# Newtech_Music_Board.net
KiCad netlist of a schematic drawn in EAGLE
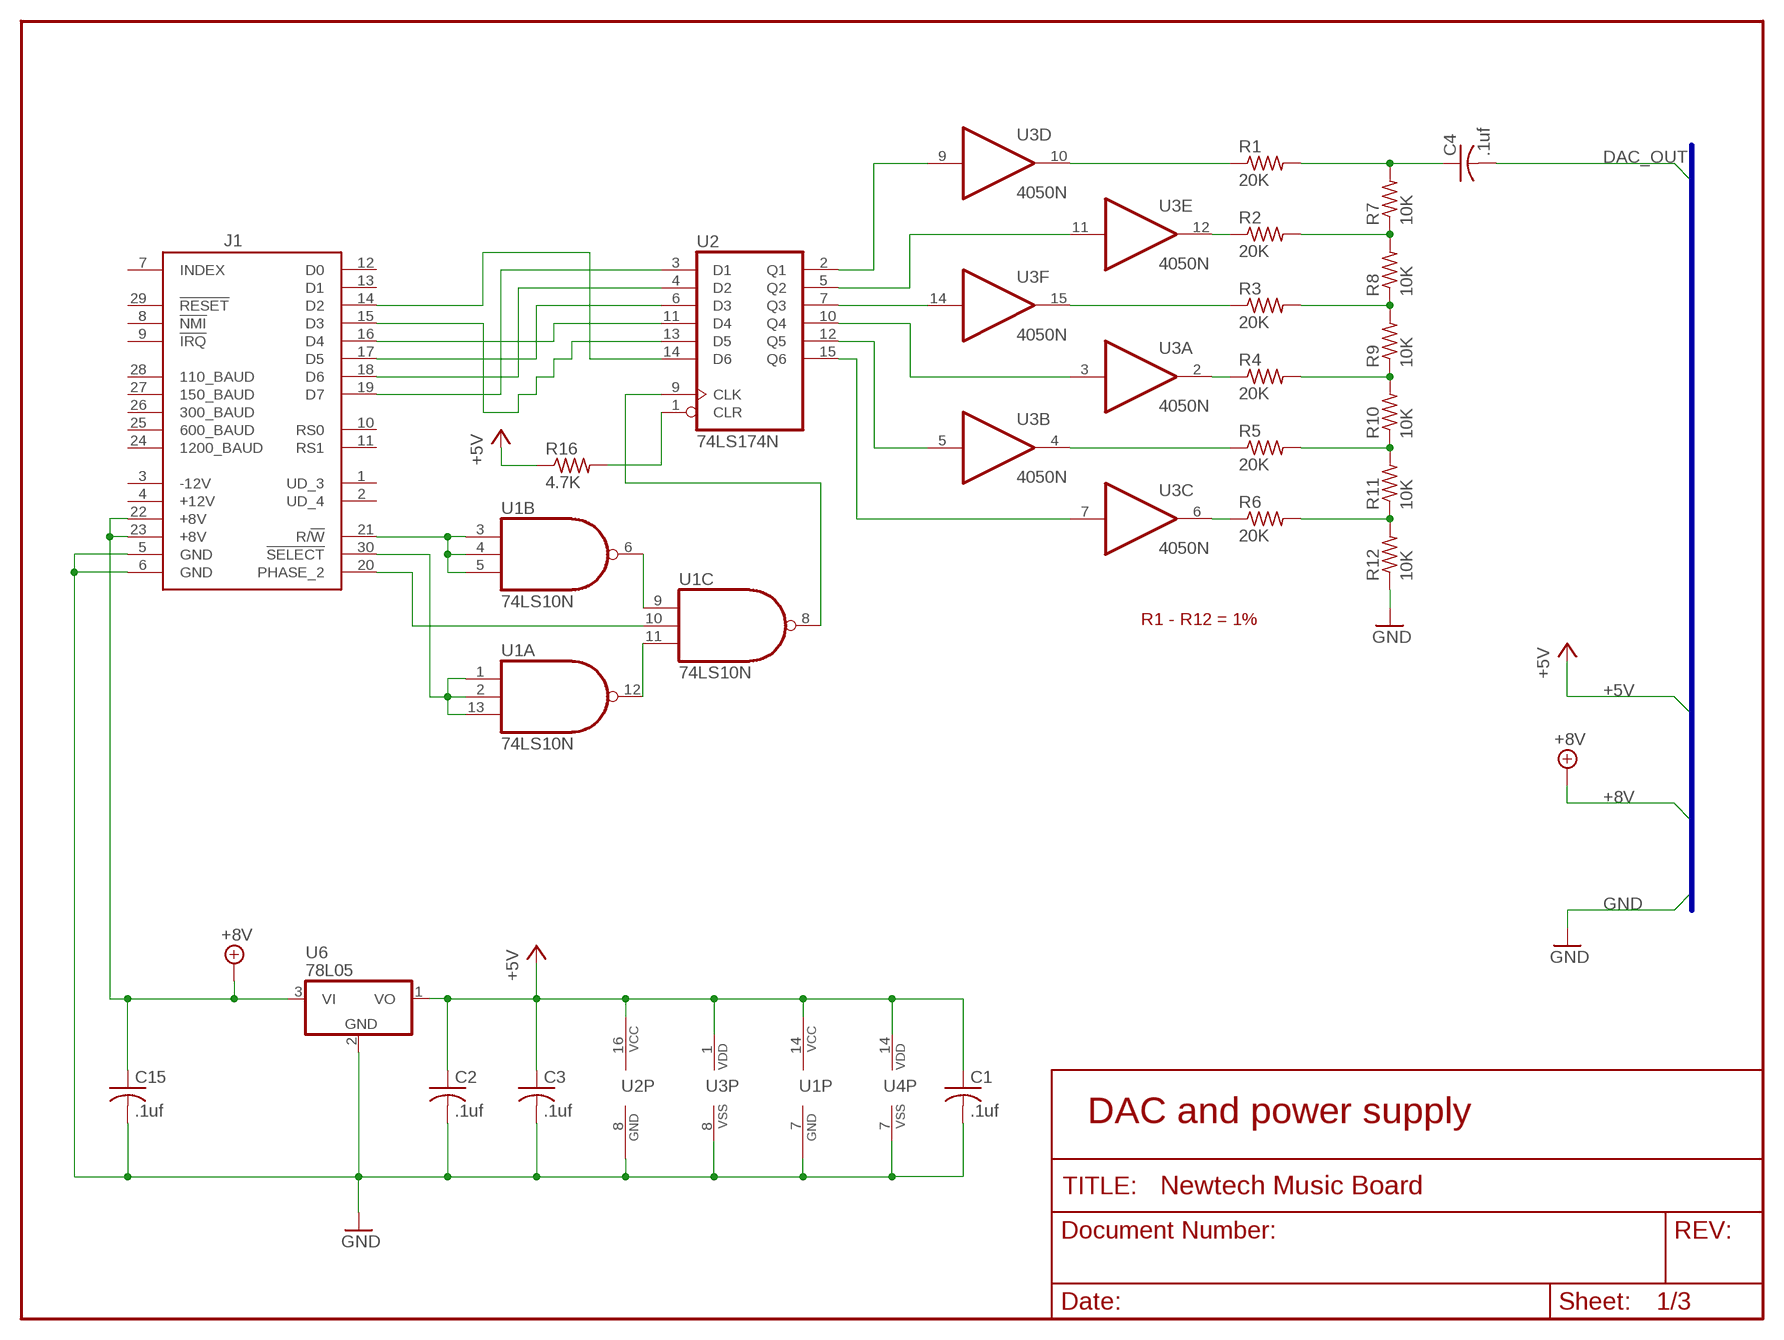
[diagram p0: schematic, sheet 1]
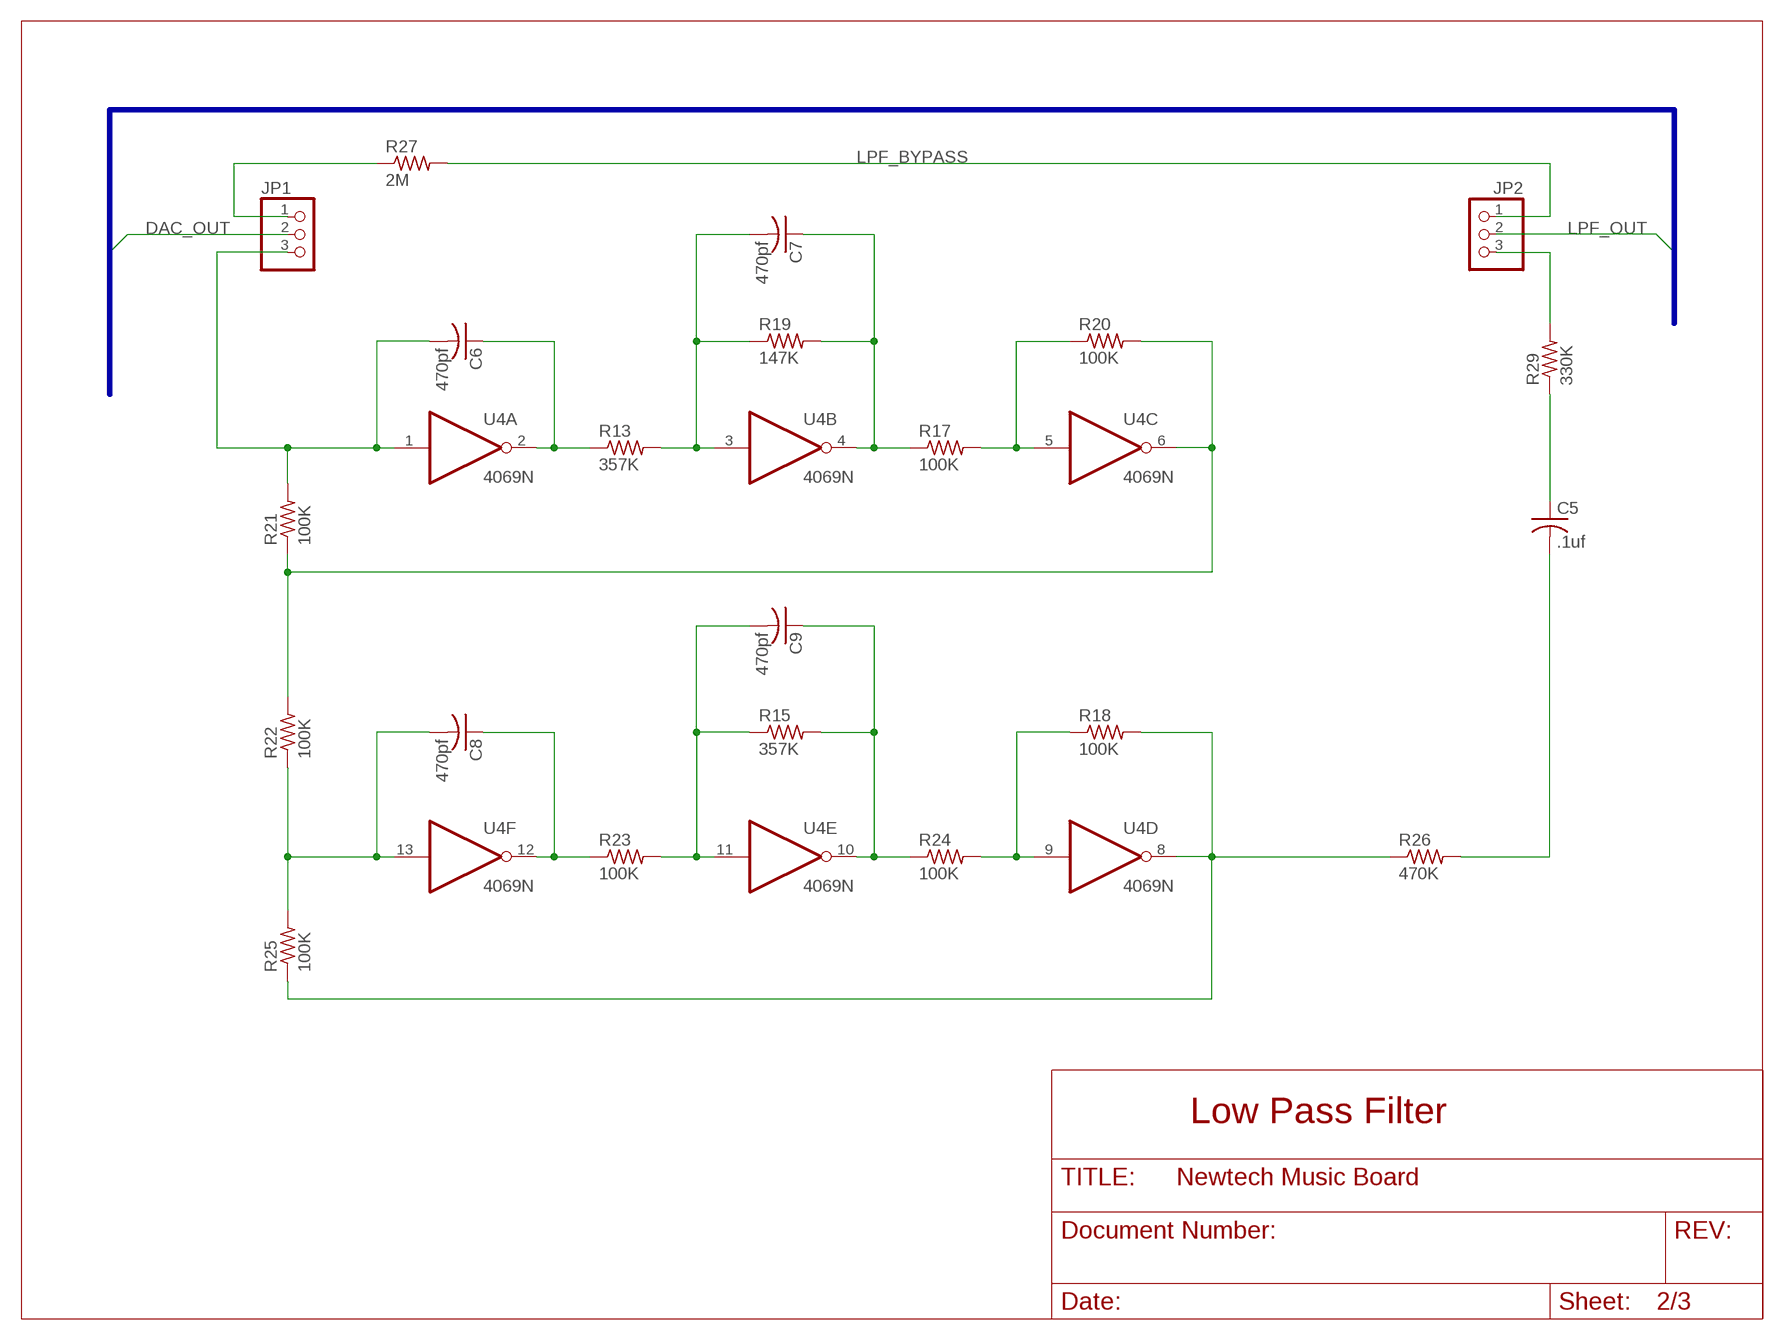
[diagram p1: schematic, sheet 2]
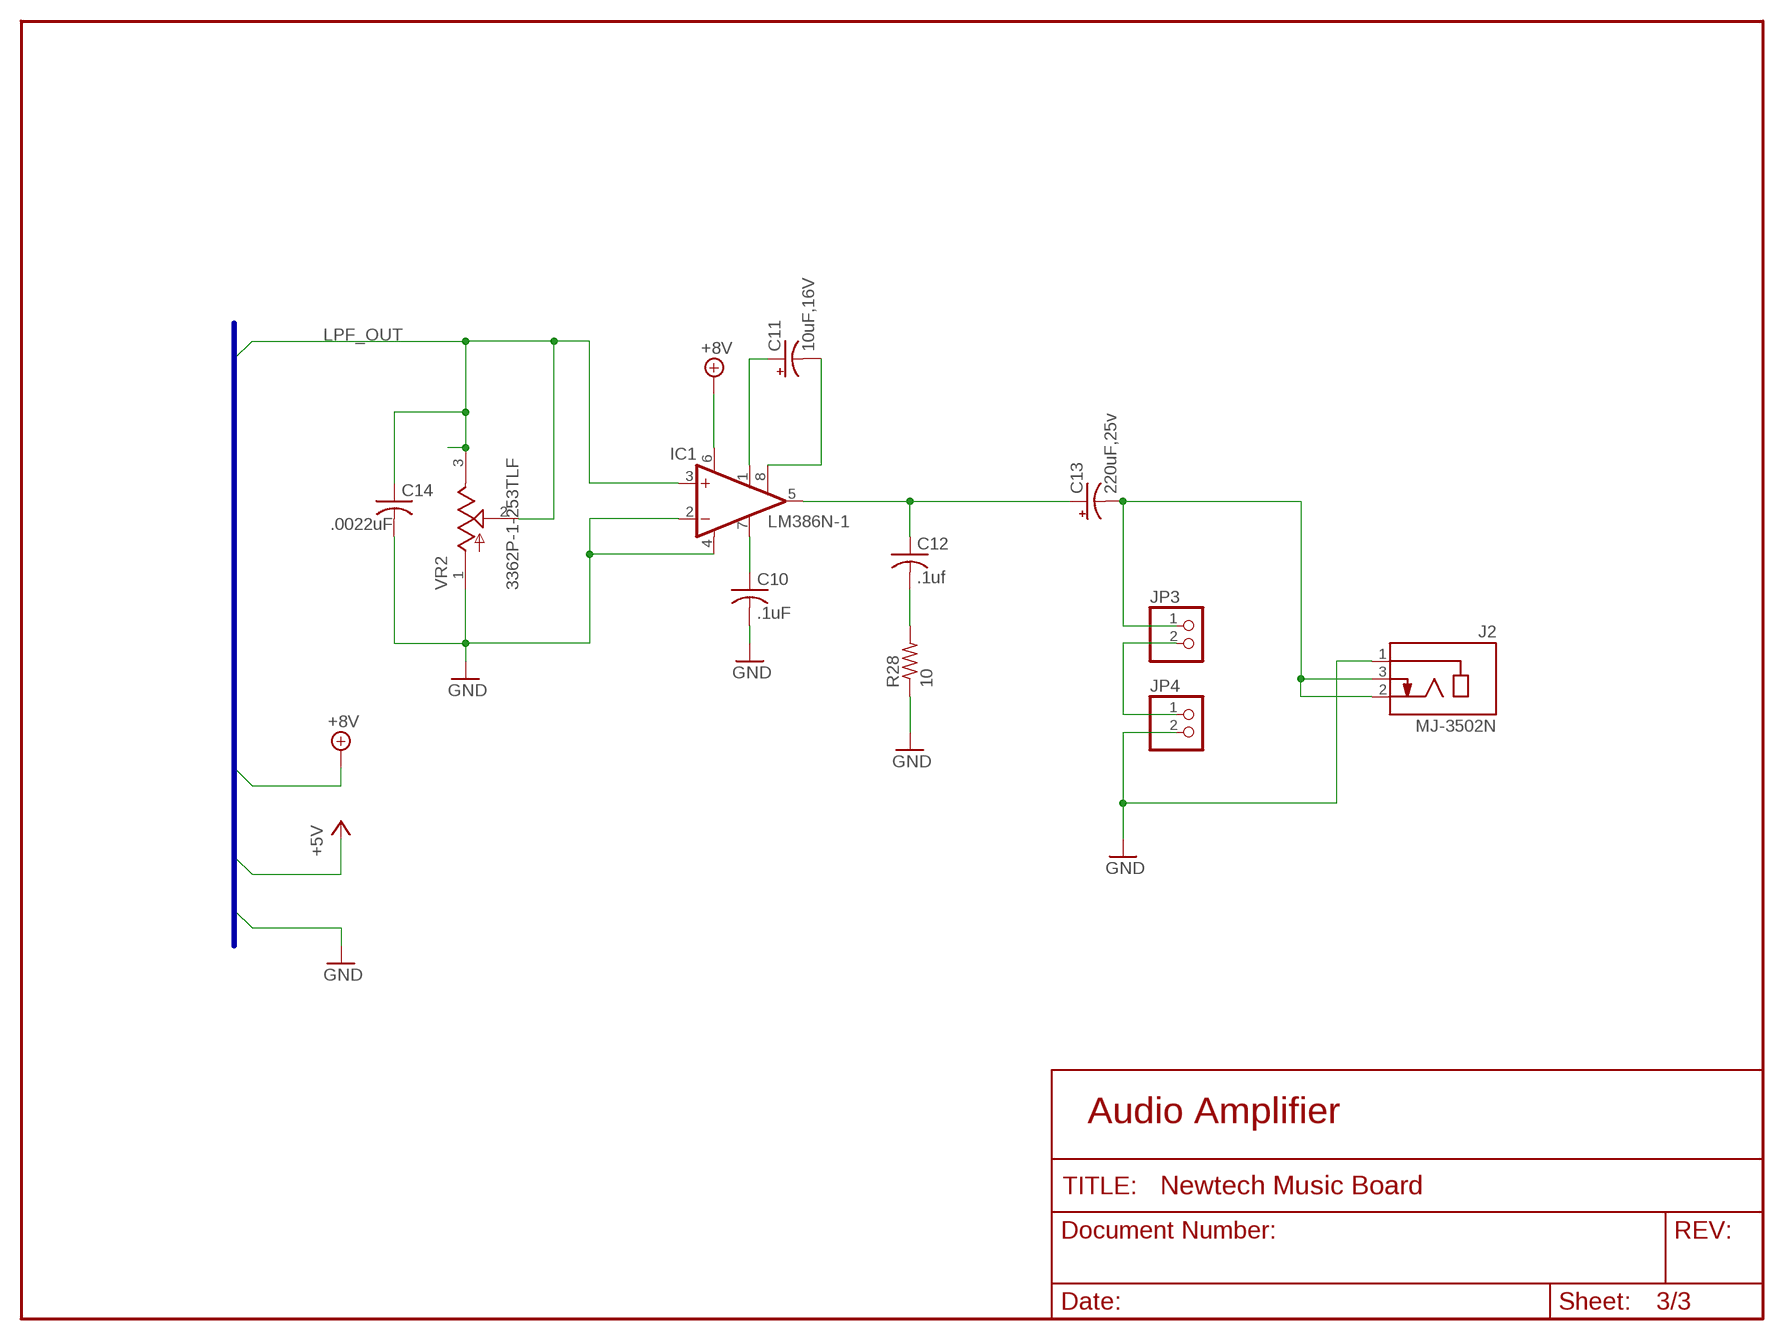
[diagram p2: schematic, sheet 3]

(export (version "E")
  (design (tool "Eeschema 10.0.6"))
  (components
    (comp (ref "C10")
      (value ".1uF")
      (footprint "eagle-import:C025-025X050")
      (libsource (lib "eagle-import") (part "rcl_334_C-US025-025X050"))
    )
    (comp (ref "C11")
      (value "10uF,16V")
      (footprint "eagle-import:E2,5-6")
      (libsource (lib "eagle-import") (part "CPOL-USE2.5-6"))
    )
    (comp (ref "C12")
      (value ".1uf")
      (footprint "eagle-import:C025-025X050")
      (libsource (lib "eagle-import") (part "C-US025-025X050"))
    )
    (comp (ref "C13")
      (value "220uF,25v")
      (footprint "eagle-import:E25-9")
      (libsource (lib "eagle-import") (part "CPOL-USE25-9AXIAL"))
    )
    (comp (ref "C14")
      (value ".0022uF")
      (footprint "eagle-import:C025-025X050")
      (libsource (lib "eagle-import") (part "C-US025-025X050"))
    )
    (comp (ref "IC1")
      (value "LM386N-1")
      (footprint "eagle-import:DIL08")
      (libsource (lib "eagle-import") (part "LM386?-N1"))
    )
    (comp (ref "J2")
      (value "MJ-3502N")
      (footprint "eagle-import:CUI_MJ-3502N")
      (fields (field (name "MF") "CUI Devices"))
      (libsource (lib "eagle-import") (part "MJ-3502N"))
    )
    (comp (ref "JP3")
      (value "PINHD-1X2")
      (footprint "eagle-import:1X02")
      (libsource (lib "eagle-import") (part "PINHD-1X2"))
    )
    (comp (ref "JP4")
      (value "PINHD-1X2")
      (footprint "eagle-import:1X02")
      (libsource (lib "eagle-import") (part "PINHD-1X2"))
    )
    (comp (ref "R28")
      (value "10")
      (footprint "eagle-import:0204_7")
      (libsource (lib "eagle-import") (part "rcl_334_R-US_0204/7"))
    )
    (comp (ref "VR2")
      (value "3362P-1-253TLF")
      (footprint "eagle-import:TRIM_3362P-1-253TLF")
      (fields (field (name "MF") "Bourns") (field (name "MP") "3362P-1-205LF"))
      (libsource (lib "eagle-import") (part "3362P-1-253TLF"))
    )
    (comp (ref "C5")
      (value ".1uf")
      (footprint "eagle-import:C025-025X050")
      (libsource (lib "eagle-import") (part "C-US025-025X050"))
    )
    (comp (ref "C6")
      (value "470pf")
      (footprint "eagle-import:C050-045X075")
      (libsource (lib "eagle-import") (part "C-US050-045X075"))
    )
    (comp (ref "C7")
      (value "470pf")
      (footprint "eagle-import:C050-045X075")
      (libsource (lib "eagle-import") (part "C-US050-045X075"))
    )
    (comp (ref "C8")
      (value "470pf")
      (footprint "eagle-import:C050-045X075")
      (libsource (lib "eagle-import") (part "C-US050-045X075"))
    )
    (comp (ref "C9")
      (value "470pf")
      (footprint "eagle-import:C050-045X075")
      (libsource (lib "eagle-import") (part "C-US050-045X075"))
    )
    (comp (ref "JP1")
      (value "PINHD-1X3")
      (footprint "eagle-import:1X03")
      (libsource (lib "eagle-import") (part "PINHD-1X3"))
    )
    (comp (ref "JP2")
      (value "PINHD-1X3")
      (footprint "eagle-import:1X03")
      (libsource (lib "eagle-import") (part "PINHD-1X3"))
    )
    (comp (ref "R13")
      (value "357K")
      (footprint "eagle-import:0204_7")
      (libsource (lib "eagle-import") (part "R-US_0204/7"))
    )
    (comp (ref "R15")
      (value "357K")
      (footprint "eagle-import:0204_7")
      (libsource (lib "eagle-import") (part "R-US_0204/7"))
    )
    (comp (ref "R17")
      (value "100K")
      (footprint "eagle-import:0204_7")
      (libsource (lib "eagle-import") (part "R-US_0204/7"))
    )
    (comp (ref "R18")
      (value "100K")
      (footprint "eagle-import:0204_7")
      (libsource (lib "eagle-import") (part "R-US_0204/7"))
    )
    (comp (ref "R19")
      (value "147K")
      (footprint "eagle-import:0204_7")
      (libsource (lib "eagle-import") (part "R-US_0204/7"))
    )
    (comp (ref "R20")
      (value "100K")
      (footprint "eagle-import:0204_7")
      (libsource (lib "eagle-import") (part "R-US_0204/7"))
    )
    (comp (ref "R21")
      (value "100K")
      (footprint "eagle-import:0204_7")
      (libsource (lib "eagle-import") (part "R-US_0204/7"))
    )
    (comp (ref "R22")
      (value "100K")
      (footprint "eagle-import:0204_7")
      (libsource (lib "eagle-import") (part "R-US_0204/7"))
    )
    (comp (ref "R23")
      (value "100K")
      (footprint "eagle-import:0204_7")
      (libsource (lib "eagle-import") (part "R-US_0204/7"))
    )
    (comp (ref "R24")
      (value "100K")
      (footprint "eagle-import:0204_7")
      (libsource (lib "eagle-import") (part "R-US_0204/7"))
    )
    (comp (ref "R25")
      (value "100K")
      (footprint "eagle-import:0204_7")
      (libsource (lib "eagle-import") (part "R-US_0204/7"))
    )
    (comp (ref "R26")
      (value "470K")
      (footprint "eagle-import:0204_7")
      (libsource (lib "eagle-import") (part "R-US_0204/7"))
    )
    (comp (ref "R27")
      (value "2M")
      (footprint "eagle-import:0204_7")
      (libsource (lib "eagle-import") (part "R-US_0204/7"))
    )
    (comp (ref "R29")
      (value "330K")
      (footprint "eagle-import:0204_7")
      (libsource (lib "eagle-import") (part "R-US_0204/7"))
    )
    (comp (ref "U4")
      (value "4069N")
      (footprint "eagle-import:DIL14")
      (libsource (lib "eagle-import") (part "4069N"))
    )
    (comp (ref "C1")
      (value ".1uf")
      (footprint "eagle-import:C025-025X050")
      (libsource (lib "eagle-import") (part "C-US025-025X050"))
    )
    (comp (ref "C2")
      (value ".1uf")
      (footprint "eagle-import:C025-025X050")
      (libsource (lib "eagle-import") (part "C-US025-025X050"))
    )
    (comp (ref "C3")
      (value ".1uf")
      (footprint "eagle-import:C025-025X050")
      (libsource (lib "eagle-import") (part "C-US025-025X050"))
    )
    (comp (ref "C4")
      (value ".1uf")
      (footprint "eagle-import:C025-024X044")
      (libsource (lib "eagle-import") (part "C-US025-024X044"))
    )
    (comp (ref "C15")
      (value ".1uf")
      (footprint "eagle-import:C025-025X050")
      (libsource (lib "eagle-import") (part "C-US025-025X050"))
    )
    (comp (ref "J1")
      (value "SS-30_BOARD_CONNECTOR")
      (footprint "eagle-import:SS-30_BOARD_CONNECTOR")
      (libsource (lib "eagle-import") (part "SS-30_BOARD_CONNECTOR"))
    )
    (comp (ref "R1")
      (value "20K")
      (footprint "eagle-import:0204_7")
      (libsource (lib "eagle-import") (part "R-US_0204/7"))
    )
    (comp (ref "R2")
      (value "20K")
      (footprint "eagle-import:0204_7")
      (libsource (lib "eagle-import") (part "R-US_0204/7"))
    )
    (comp (ref "R3")
      (value "20K")
      (footprint "eagle-import:0204_7")
      (libsource (lib "eagle-import") (part "R-US_0204/7"))
    )
    (comp (ref "R4")
      (value "20K")
      (footprint "eagle-import:0204_7")
      (libsource (lib "eagle-import") (part "R-US_0204/7"))
    )
    (comp (ref "R5")
      (value "20K")
      (footprint "eagle-import:0204_7")
      (libsource (lib "eagle-import") (part "R-US_0204/7"))
    )
    (comp (ref "R6")
      (value "20K")
      (footprint "eagle-import:0204_7")
      (libsource (lib "eagle-import") (part "R-US_0204/7"))
    )
    (comp (ref "R7")
      (value "10K")
      (footprint "eagle-import:0204_7")
      (libsource (lib "eagle-import") (part "R-US_0204/7"))
    )
    (comp (ref "R8")
      (value "10K")
      (footprint "eagle-import:0204_7")
      (libsource (lib "eagle-import") (part "R-US_0204/7"))
    )
    (comp (ref "R9")
      (value "10K")
      (footprint "eagle-import:0204_7")
      (libsource (lib "eagle-import") (part "R-US_0204/7"))
    )
    (comp (ref "R10")
      (value "10K")
      (footprint "eagle-import:0204_7")
      (libsource (lib "eagle-import") (part "R-US_0204/7"))
    )
    (comp (ref "R11")
      (value "10K")
      (footprint "eagle-import:0204_7")
      (libsource (lib "eagle-import") (part "R-US_0204/7"))
    )
    (comp (ref "R12")
      (value "10K")
      (footprint "eagle-import:0204_7")
      (libsource (lib "eagle-import") (part "R-US_0204/7"))
    )
    (comp (ref "R16")
      (value "4.7K")
      (footprint "eagle-import:0204_7")
      (libsource (lib "eagle-import") (part "R-US_0204/7"))
    )
    (comp (ref "U1")
      (value "74LS10N")
      (footprint "eagle-import:DIL14")
      (libsource (lib "eagle-import") (part "7410NLS"))
    )
    (comp (ref "U2")
      (value "74LS174N")
      (footprint "eagle-import:DIL16")
      (libsource (lib "eagle-import") (part "74174NLS"))
    )
    (comp (ref "U3")
      (value "4050N")
      (footprint "eagle-import:DIL16")
      (libsource (lib "eagle-import") (part "4050N"))
    )
    (comp (ref "U6")
      (value "78L05")
      (footprint "eagle-import:TO-92")
      (fields (field (name "MF") "STMicroelectronics") (field (name "MP") "78L05ACZ"))
      (libsource (lib "eagle-import") (part "78L05ACZ"))
    )
  )
  (nets
    (net (code "1") (name "+5V") (class "Default")
      (node (ref "C1") (pin "1") (pinfunction "1_1") (pintype "passive"))
      (node (ref "C2") (pin "1") (pinfunction "1_1") (pintype "passive"))
      (node (ref "C3") (pin "1") (pinfunction "1_1") (pintype "passive"))
      (node (ref "R16") (pin "1") (pinfunction "1_1") (pintype "passive"))
      (node (ref "U1") (pin "14") (pinfunction "VCC_14") (pintype "power_in"))
      (node (ref "U2") (pin "16") (pinfunction "VCC_16") (pintype "power_in"))
      (node (ref "U3") (pin "1") (pinfunction "VDD_1") (pintype "power_in"))
      (node (ref "U4") (pin "14") (pinfunction "VDD_14") (pintype "power_in"))
      (node (ref "U6") (pin "1") (pinfunction "VO_1") (pintype "passive"))
    )
    (net (code "2") (name "+8V") (class "Default")
      (node (ref "C15") (pin "1") (pinfunction "1_1") (pintype "passive"))
      (node (ref "IC1") (pin "6") (pinfunction "VS_6") (pintype "power_in"))
      (node (ref "J1") (pin "22") (pinfunction "+8V_22") (pintype "power_in"))
      (node (ref "J1") (pin "23") (pinfunction "+8V_23") (pintype "power_in"))
      (node (ref "U6") (pin "3") (pinfunction "VI_3") (pintype "input"))
    )
    (net (code "3") (name "+12V") (class "Default")
      (node (ref "J1") (pin "4") (pinfunction "+12V_4") (pintype "power_in"))
    )
    (net (code "4") (name "-12V") (class "Default")
      (node (ref "J1") (pin "3") (pinfunction "-12V_3") (pintype "power_in"))
    )
    (net (code "5") (name "DAC_OUT") (class "Default")
      (node (ref "C4") (pin "2") (pinfunction "2_2") (pintype "passive"))
      (node (ref "JP1") (pin "2") (pinfunction "2_2") (pintype "passive"))
    )
    (net (code "6") (name "GND") (class "Default")
      (node (ref "C1") (pin "2") (pinfunction "2_2") (pintype "passive"))
      (node (ref "C10") (pin "2") (pinfunction "2_2") (pintype "passive"))
      (node (ref "C14") (pin "2") (pinfunction "2_2") (pintype "passive"))
      (node (ref "C15") (pin "2") (pinfunction "2_2") (pintype "passive"))
      (node (ref "C2") (pin "2") (pinfunction "2_2") (pintype "passive"))
      (node (ref "C3") (pin "2") (pinfunction "2_2") (pintype "passive"))
      (node (ref "IC1") (pin "2") (pinfunction "-IN_2") (pintype "input"))
      (node (ref "IC1") (pin "4") (pinfunction "GND_4") (pintype "power_in"))
      (node (ref "J1") (pin "5") (pinfunction "GND_5") (pintype "power_in"))
      (node (ref "J1") (pin "6") (pinfunction "GND_6") (pintype "power_in"))
      (node (ref "J2") (pin "1") (pinfunction "1_1") (pintype "passive"))
      (node (ref "JP4") (pin "2") (pinfunction "2_2") (pintype "passive"))
      (node (ref "R12") (pin "1") (pinfunction "1_1") (pintype "passive"))
      (node (ref "R28") (pin "1") (pinfunction "1_1") (pintype "passive"))
      (node (ref "U1") (pin "7") (pinfunction "GND_7") (pintype "power_in"))
      (node (ref "U2") (pin "8") (pinfunction "GND_8") (pintype "power_in"))
      (node (ref "U3") (pin "8") (pinfunction "VSS_8") (pintype "power_in"))
      (node (ref "U4") (pin "7") (pinfunction "VSS_7") (pintype "power_in"))
      (node (ref "U6") (pin "2") (pinfunction "GND_2") (pintype "passive"))
      (node (ref "VR2") (pin "1") (pinfunction "CCW_1") (pintype "passive"))
    )
    (net (code "7") (name "LPF_BYPASS") (class "Default")
      (node (ref "JP2") (pin "1") (pinfunction "1_1") (pintype "passive"))
      (node (ref "R27") (pin "2") (pinfunction "2_2") (pintype "passive"))
    )
    (net (code "8") (name "LPF_OUT") (class "Default")
      (node (ref "C14") (pin "1") (pinfunction "1_1") (pintype "passive"))
      (node (ref "IC1") (pin "3") (pinfunction "+IN_3") (pintype "input"))
      (node (ref "JP2") (pin "2") (pinfunction "2_2") (pintype "passive"))
      (node (ref "VR2") (pin "2") (pinfunction "WIPER_2") (pintype "passive"))
      (node (ref "VR2") (pin "3") (pinfunction "CW_3") (pintype "passive"))
    )
    (net (code "9") (name "Net-(C4-Pad1)") (class "Default")
      (node (ref "C4") (pin "1") (pinfunction "1_1") (pintype "passive"))
      (node (ref "R1") (pin "2") (pinfunction "2_2") (pintype "passive"))
      (node (ref "R7") (pin "2") (pinfunction "2_2") (pintype "passive"))
    )
    (net (code "10") (name "Net-(C5-Pad1)") (class "Default")
      (node (ref "C5") (pin "1") (pinfunction "1_1") (pintype "passive"))
      (node (ref "R29") (pin "1") (pinfunction "1_1") (pintype "passive"))
    )
    (net (code "11") (name "Net-(C5-Pad2)") (class "Default")
      (node (ref "C5") (pin "2") (pinfunction "2_2") (pintype "passive"))
      (node (ref "R26") (pin "2") (pinfunction "2_2") (pintype "passive"))
    )
    (net (code "12") (name "Net-(C11-Pad+)") (class "Default")
      (node (ref "C11") (pin "+") (pinfunction "+_+") (pintype "passive"))
      (node (ref "IC1") (pin "1") (pinfunction "GAIN_1") (pintype "passive"))
    )
    (net (code "13") (name "Net-(C11-Pad-)") (class "Default")
      (node (ref "C11") (pin "-") (pinfunction "-_-") (pintype "passive"))
      (node (ref "IC1") (pin "8") (pinfunction "GAIN_8") (pintype "passive"))
    )
    (net (code "14") (name "Net-(C12-Pad2)") (class "Default")
      (node (ref "C12") (pin "2") (pinfunction "2_2") (pintype "passive"))
      (node (ref "R28") (pin "2") (pinfunction "2_2") (pintype "passive"))
    )
    (net (code "15") (name "Net-(C13-Pad-)") (class "Default")
      (node (ref "C13") (pin "-") (pinfunction "-_-") (pintype "passive"))
      (node (ref "J2") (pin "2") (pinfunction "2_2") (pintype "passive"))
      (node (ref "J2") (pin "3") (pinfunction "3_3") (pintype "passive"))
      (node (ref "JP3") (pin "1") (pinfunction "1_1") (pintype "passive"))
    )
    (net (code "16") (name "Net-(IC1-BYPASS)") (class "Default")
      (node (ref "C10") (pin "1") (pinfunction "1_1") (pintype "passive"))
      (node (ref "IC1") (pin "7") (pinfunction "BYPASS_7") (pintype "passive"))
    )
    (net (code "17") (name "Net-(IC1-OUT)") (class "Default")
      (node (ref "C12") (pin "1") (pinfunction "1_1") (pintype "passive"))
      (node (ref "C13") (pin "+") (pinfunction "+_+") (pintype "passive"))
      (node (ref "IC1") (pin "5") (pinfunction "OUT_5") (pintype "output"))
    )
    (net (code "18") (name "Net-(J1-D2)") (class "Default")
      (node (ref "J1") (pin "14") (pinfunction "D2_14") (pintype "bidirectional"))
      (node (ref "U2") (pin "14") (pinfunction "D6_14") (pintype "input"))
    )
    (net (code "19") (name "Net-(J1-D3)") (class "Default")
      (node (ref "J1") (pin "15") (pinfunction "D3_15") (pintype "bidirectional"))
      (node (ref "U2") (pin "13") (pinfunction "D5_13") (pintype "input"))
    )
    (net (code "20") (name "Net-(J1-D4)") (class "Default")
      (node (ref "J1") (pin "16") (pinfunction "D4_16") (pintype "bidirectional"))
      (node (ref "U2") (pin "11") (pinfunction "D4_11") (pintype "input"))
    )
    (net (code "21") (name "Net-(J1-D5)") (class "Default")
      (node (ref "J1") (pin "17") (pinfunction "D5_17") (pintype "bidirectional"))
      (node (ref "U2") (pin "6") (pinfunction "D3_6") (pintype "input"))
    )
    (net (code "22") (name "Net-(J1-D6)") (class "Default")
      (node (ref "J1") (pin "18") (pinfunction "D6_18") (pintype "bidirectional"))
      (node (ref "U2") (pin "4") (pinfunction "D2_4") (pintype "input"))
    )
    (net (code "23") (name "Net-(J1-D7)") (class "Default")
      (node (ref "J1") (pin "19") (pinfunction "D7_19") (pintype "bidirectional"))
      (node (ref "U2") (pin "3") (pinfunction "D1_3") (pintype "input"))
    )
    (net (code "24") (name "Net-(J1-PHASE_2)") (class "Default")
      (node (ref "J1") (pin "20") (pinfunction "PHASE_2_20") (pintype "bidirectional"))
      (node (ref "U1") (pin "10") (pinfunction "I1_10") (pintype "input"))
    )
    (net (code "25") (name "Net-(J1-R{slash}~{W})") (class "Default")
      (node (ref "J1") (pin "21") (pinfunction "R/~{W}_21") (pintype "bidirectional"))
      (node (ref "U1") (pin "3") (pinfunction "I0_3") (pintype "input"))
      (node (ref "U1") (pin "4") (pinfunction "I1_4") (pintype "input"))
      (node (ref "U1") (pin "5") (pinfunction "I2_5") (pintype "input"))
    )
    (net (code "26") (name "Net-(J1-~{SELECT})") (class "Default")
      (node (ref "J1") (pin "30") (pinfunction "~{SELECT}_30") (pintype "bidirectional"))
      (node (ref "U1") (pin "1") (pinfunction "I0_1") (pintype "input"))
      (node (ref "U1") (pin "13") (pinfunction "I2_13") (pintype "input"))
      (node (ref "U1") (pin "2") (pinfunction "I1_2") (pintype "input"))
    )
    (net (code "27") (name "Net-(JP1-Pad1)") (class "Default")
      (node (ref "JP1") (pin "1") (pinfunction "1_1") (pintype "passive"))
      (node (ref "R27") (pin "1") (pinfunction "1_1") (pintype "passive"))
    )
    (net (code "28") (name "Net-(JP2-Pad3)") (class "Default")
      (node (ref "JP2") (pin "3") (pinfunction "3_3") (pintype "passive"))
      (node (ref "R29") (pin "2") (pinfunction "2_2") (pintype "passive"))
    )
    (net (code "29") (name "Net-(JP3-Pad2)") (class "Default")
      (node (ref "JP3") (pin "2") (pinfunction "2_2") (pintype "passive"))
      (node (ref "JP4") (pin "1") (pinfunction "1_1") (pintype "passive"))
    )
    (net (code "30") (name "Net-(R2-Pad2)") (class "Default")
      (node (ref "R2") (pin "2") (pinfunction "2_2") (pintype "passive"))
      (node (ref "R7") (pin "1") (pinfunction "1_1") (pintype "passive"))
      (node (ref "R8") (pin "2") (pinfunction "2_2") (pintype "passive"))
    )
    (net (code "31") (name "Net-(R3-Pad2)") (class "Default")
      (node (ref "R3") (pin "2") (pinfunction "2_2") (pintype "passive"))
      (node (ref "R8") (pin "1") (pinfunction "1_1") (pintype "passive"))
      (node (ref "R9") (pin "2") (pinfunction "2_2") (pintype "passive"))
    )
    (net (code "32") (name "Net-(R10-Pad1)") (class "Default")
      (node (ref "R10") (pin "1") (pinfunction "1_1") (pintype "passive"))
      (node (ref "R11") (pin "2") (pinfunction "2_2") (pintype "passive"))
      (node (ref "R5") (pin "2") (pinfunction "2_2") (pintype "passive"))
    )
    (net (code "33") (name "Net-(R10-Pad2)") (class "Default")
      (node (ref "R10") (pin "2") (pinfunction "2_2") (pintype "passive"))
      (node (ref "R4") (pin "2") (pinfunction "2_2") (pintype "passive"))
      (node (ref "R9") (pin "1") (pinfunction "1_1") (pintype "passive"))
    )
    (net (code "34") (name "Net-(R11-Pad1)") (class "Default")
      (node (ref "R11") (pin "1") (pinfunction "1_1") (pintype "passive"))
      (node (ref "R12") (pin "2") (pinfunction "2_2") (pintype "passive"))
      (node (ref "R6") (pin "2") (pinfunction "2_2") (pintype "passive"))
    )
    (net (code "35") (name "Net-(U1A-O)") (class "Default")
      (node (ref "U1") (pin "11") (pinfunction "I2_11") (pintype "input"))
      (node (ref "U1") (pin "12") (pinfunction "O_12") (pintype "output"))
    )
    (net (code "36") (name "Net-(U1B-O)") (class "Default")
      (node (ref "U1") (pin "6") (pinfunction "O_6") (pintype "output"))
      (node (ref "U1") (pin "9") (pinfunction "I0_9") (pintype "input"))
    )
    (net (code "37") (name "Net-(U1C-O)") (class "Default")
      (node (ref "U1") (pin "8") (pinfunction "O_8") (pintype "output"))
      (node (ref "U2") (pin "9") (pinfunction "CLK_9") (pintype "input"))
    )
    (net (code "38") (name "Net-(U2A-CLR)") (class "Default")
      (node (ref "R16") (pin "2") (pinfunction "2_2") (pintype "passive"))
      (node (ref "U2") (pin "1") (pinfunction "CLR_1") (pintype "input"))
    )
    (net (code "39") (name "Net-(U2A-Q1)") (class "Default")
      (node (ref "U2") (pin "2") (pinfunction "Q1_2") (pintype "output"))
      (node (ref "U3") (pin "9") (pinfunction "I_9") (pintype "input"))
    )
    (net (code "40") (name "Net-(U2A-Q2)") (class "Default")
      (node (ref "U2") (pin "5") (pinfunction "Q2_5") (pintype "output"))
      (node (ref "U3") (pin "11") (pinfunction "I_11") (pintype "input"))
    )
    (net (code "41") (name "Net-(U2A-Q3)") (class "Default")
      (node (ref "U2") (pin "7") (pinfunction "Q3_7") (pintype "output"))
      (node (ref "U3") (pin "14") (pinfunction "I_14") (pintype "input"))
    )
    (net (code "42") (name "Net-(U2A-Q4)") (class "Default")
      (node (ref "U2") (pin "10") (pinfunction "Q4_10") (pintype "output"))
      (node (ref "U3") (pin "3") (pinfunction "I_3") (pintype "input"))
    )
    (net (code "43") (name "Net-(U2A-Q5)") (class "Default")
      (node (ref "U2") (pin "12") (pinfunction "Q5_12") (pintype "output"))
      (node (ref "U3") (pin "5") (pinfunction "I_5") (pintype "input"))
    )
    (net (code "44") (name "Net-(U2A-Q6)") (class "Default")
      (node (ref "U2") (pin "15") (pinfunction "Q6_15") (pintype "output"))
      (node (ref "U3") (pin "7") (pinfunction "I_7") (pintype "input"))
    )
    (net (code "45") (name "Net-(U3A-O)") (class "Default")
      (node (ref "R4") (pin "1") (pinfunction "1_1") (pintype "passive"))
      (node (ref "U3") (pin "2") (pinfunction "O_2") (pintype "output"))
    )
    (net (code "46") (name "Net-(U3B-O)") (class "Default")
      (node (ref "R5") (pin "1") (pinfunction "1_1") (pintype "passive"))
      (node (ref "U3") (pin "4") (pinfunction "O_4") (pintype "output"))
    )
    (net (code "47") (name "Net-(U3C-O)") (class "Default")
      (node (ref "R6") (pin "1") (pinfunction "1_1") (pintype "passive"))
      (node (ref "U3") (pin "6") (pinfunction "O_6") (pintype "output"))
    )
    (net (code "48") (name "Net-(U3D-O)") (class "Default")
      (node (ref "R1") (pin "1") (pinfunction "1_1") (pintype "passive"))
      (node (ref "U3") (pin "10") (pinfunction "O_10") (pintype "output"))
    )
    (net (code "49") (name "Net-(U3E-O)") (class "Default")
      (node (ref "R2") (pin "1") (pinfunction "1_1") (pintype "passive"))
      (node (ref "U3") (pin "12") (pinfunction "O_12") (pintype "output"))
    )
    (net (code "50") (name "Net-(U3F-O)") (class "Default")
      (node (ref "R3") (pin "1") (pinfunction "1_1") (pintype "passive"))
      (node (ref "U3") (pin "15") (pinfunction "O_15") (pintype "output"))
    )
    (net (code "51") (name "Net-(U4A-I)") (class "Default")
      (node (ref "C6") (pin "2") (pinfunction "2_2") (pintype "passive"))
      (node (ref "JP1") (pin "3") (pinfunction "3_3") (pintype "passive"))
      (node (ref "R21") (pin "2") (pinfunction "2_2") (pintype "passive"))
      (node (ref "U4") (pin "1") (pinfunction "I_1") (pintype "input"))
    )
    (net (code "52") (name "Net-(U4A-O)") (class "Default")
      (node (ref "C6") (pin "1") (pinfunction "1_1") (pintype "passive"))
      (node (ref "R13") (pin "1") (pinfunction "1_1") (pintype "passive"))
      (node (ref "U4") (pin "2") (pinfunction "O_2") (pintype "output"))
    )
    (net (code "53") (name "Net-(U4B-I)") (class "Default")
      (node (ref "C7") (pin "2") (pinfunction "2_2") (pintype "passive"))
      (node (ref "R13") (pin "2") (pinfunction "2_2") (pintype "passive"))
      (node (ref "R19") (pin "1") (pinfunction "1_1") (pintype "passive"))
      (node (ref "U4") (pin "3") (pinfunction "I_3") (pintype "input"))
    )
    (net (code "54") (name "Net-(U4B-O)") (class "Default")
      (node (ref "C7") (pin "1") (pinfunction "1_1") (pintype "passive"))
      (node (ref "R17") (pin "1") (pinfunction "1_1") (pintype "passive"))
      (node (ref "R19") (pin "2") (pinfunction "2_2") (pintype "passive"))
      (node (ref "U4") (pin "4") (pinfunction "O_4") (pintype "output"))
    )
    (net (code "55") (name "Net-(U4C-I)") (class "Default")
      (node (ref "R17") (pin "2") (pinfunction "2_2") (pintype "passive"))
      (node (ref "R20") (pin "1") (pinfunction "1_1") (pintype "passive"))
      (node (ref "U4") (pin "5") (pinfunction "I_5") (pintype "input"))
    )
    (net (code "56") (name "Net-(U4C-O)") (class "Default")
      (node (ref "R20") (pin "2") (pinfunction "2_2") (pintype "passive"))
      (node (ref "R21") (pin "1") (pinfunction "1_1") (pintype "passive"))
      (node (ref "R22") (pin "2") (pinfunction "2_2") (pintype "passive"))
      (node (ref "U4") (pin "6") (pinfunction "O_6") (pintype "output"))
    )
    (net (code "57") (name "Net-(U4D-I)") (class "Default")
      (node (ref "R18") (pin "1") (pinfunction "1_1") (pintype "passive"))
      (node (ref "R24") (pin "2") (pinfunction "2_2") (pintype "passive"))
      (node (ref "U4") (pin "9") (pinfunction "I_9") (pintype "input"))
    )
    (net (code "58") (name "Net-(U4D-O)") (class "Default")
      (node (ref "R18") (pin "2") (pinfunction "2_2") (pintype "passive"))
      (node (ref "R25") (pin "1") (pinfunction "1_1") (pintype "passive"))
      (node (ref "R26") (pin "1") (pinfunction "1_1") (pintype "passive"))
      (node (ref "U4") (pin "8") (pinfunction "O_8") (pintype "output"))
    )
    (net (code "59") (name "Net-(U4E-I)") (class "Default")
      (node (ref "C9") (pin "2") (pinfunction "2_2") (pintype "passive"))
      (node (ref "R15") (pin "1") (pinfunction "1_1") (pintype "passive"))
      (node (ref "R23") (pin "2") (pinfunction "2_2") (pintype "passive"))
      (node (ref "U4") (pin "11") (pinfunction "I_11") (pintype "input"))
    )
    (net (code "60") (name "Net-(U4E-O)") (class "Default")
      (node (ref "C9") (pin "1") (pinfunction "1_1") (pintype "passive"))
      (node (ref "R15") (pin "2") (pinfunction "2_2") (pintype "passive"))
      (node (ref "R24") (pin "1") (pinfunction "1_1") (pintype "passive"))
      (node (ref "U4") (pin "10") (pinfunction "O_10") (pintype "output"))
    )
    (net (code "61") (name "Net-(U4F-I)") (class "Default")
      (node (ref "C8") (pin "2") (pinfunction "2_2") (pintype "passive"))
      (node (ref "R22") (pin "1") (pinfunction "1_1") (pintype "passive"))
      (node (ref "R25") (pin "2") (pinfunction "2_2") (pintype "passive"))
      (node (ref "U4") (pin "13") (pinfunction "I_13") (pintype "input"))
    )
    (net (code "62") (name "Net-(U4F-O)") (class "Default")
      (node (ref "C8") (pin "1") (pinfunction "1_1") (pintype "passive"))
      (node (ref "R23") (pin "1") (pinfunction "1_1") (pintype "passive"))
      (node (ref "U4") (pin "12") (pinfunction "O_12") (pintype "output"))
    )
    (net (code "63") (name "unconnected-(J1-110_BAUD-Pad28)") (class "Default")
      (node (ref "J1") (pin "28") (pinfunction "110_BAUD_28") (pintype "bidirectional"))
    )
    (net (code "64") (name "unconnected-(J1-150_BAUD-Pad27)") (class "Default")
      (node (ref "J1") (pin "27") (pinfunction "150_BAUD_27") (pintype "bidirectional"))
    )
    (net (code "65") (name "unconnected-(J1-300_BAUD-Pad26)") (class "Default")
      (node (ref "J1") (pin "26") (pinfunction "300_BAUD_26") (pintype "bidirectional"))
    )
    (net (code "66") (name "unconnected-(J1-600_BAUD-Pad25)") (class "Default")
      (node (ref "J1") (pin "25") (pinfunction "600_BAUD_25") (pintype "bidirectional"))
    )
    (net (code "67") (name "unconnected-(J1-1200_BAUD-Pad24)") (class "Default")
      (node (ref "J1") (pin "24") (pinfunction "1200_BAUD_24") (pintype "bidirectional"))
    )
    (net (code "68") (name "unconnected-(J1-D0-Pad12)") (class "Default")
      (node (ref "J1") (pin "12") (pinfunction "D0_12") (pintype "bidirectional"))
    )
    (net (code "69") (name "unconnected-(J1-D1-Pad13)") (class "Default")
      (node (ref "J1") (pin "13") (pinfunction "D1_13") (pintype "bidirectional"))
    )
    (net (code "70") (name "unconnected-(J1-INDEX-Pad7)") (class "Default")
      (node (ref "J1") (pin "7") (pinfunction "INDEX_7") (pintype "no_connect"))
    )
    (net (code "71") (name "unconnected-(J1-RS0-Pad10)") (class "Default")
      (node (ref "J1") (pin "10") (pinfunction "RS0_10") (pintype "bidirectional"))
    )
    (net (code "72") (name "unconnected-(J1-RS1-Pad11)") (class "Default")
      (node (ref "J1") (pin "11") (pinfunction "RS1_11") (pintype "bidirectional"))
    )
    (net (code "73") (name "unconnected-(J1-UD_3-Pad1)") (class "Default")
      (node (ref "J1") (pin "1") (pinfunction "UD_3_1") (pintype "bidirectional"))
    )
    (net (code "74") (name "unconnected-(J1-UD_4-Pad2)") (class "Default")
      (node (ref "J1") (pin "2") (pinfunction "UD_4_2") (pintype "bidirectional"))
    )
    (net (code "75") (name "unconnected-(J1-~{IRQ}-Pad9)") (class "Default")
      (node (ref "J1") (pin "9") (pinfunction "~{IRQ}_9") (pintype "bidirectional"))
    )
    (net (code "76") (name "unconnected-(J1-~{NMI}-Pad8)") (class "Default")
      (node (ref "J1") (pin "8") (pinfunction "~{NMI}_8") (pintype "bidirectional"))
    )
    (net (code "77") (name "unconnected-(J1-~{RESET}-Pad29)") (class "Default")
      (node (ref "J1") (pin "29") (pinfunction "~{RESET}_29") (pintype "bidirectional"))
    )
  )
)
